# linearInjector_main.net
KiCad netlist of a schematic drawn in Altium Designer
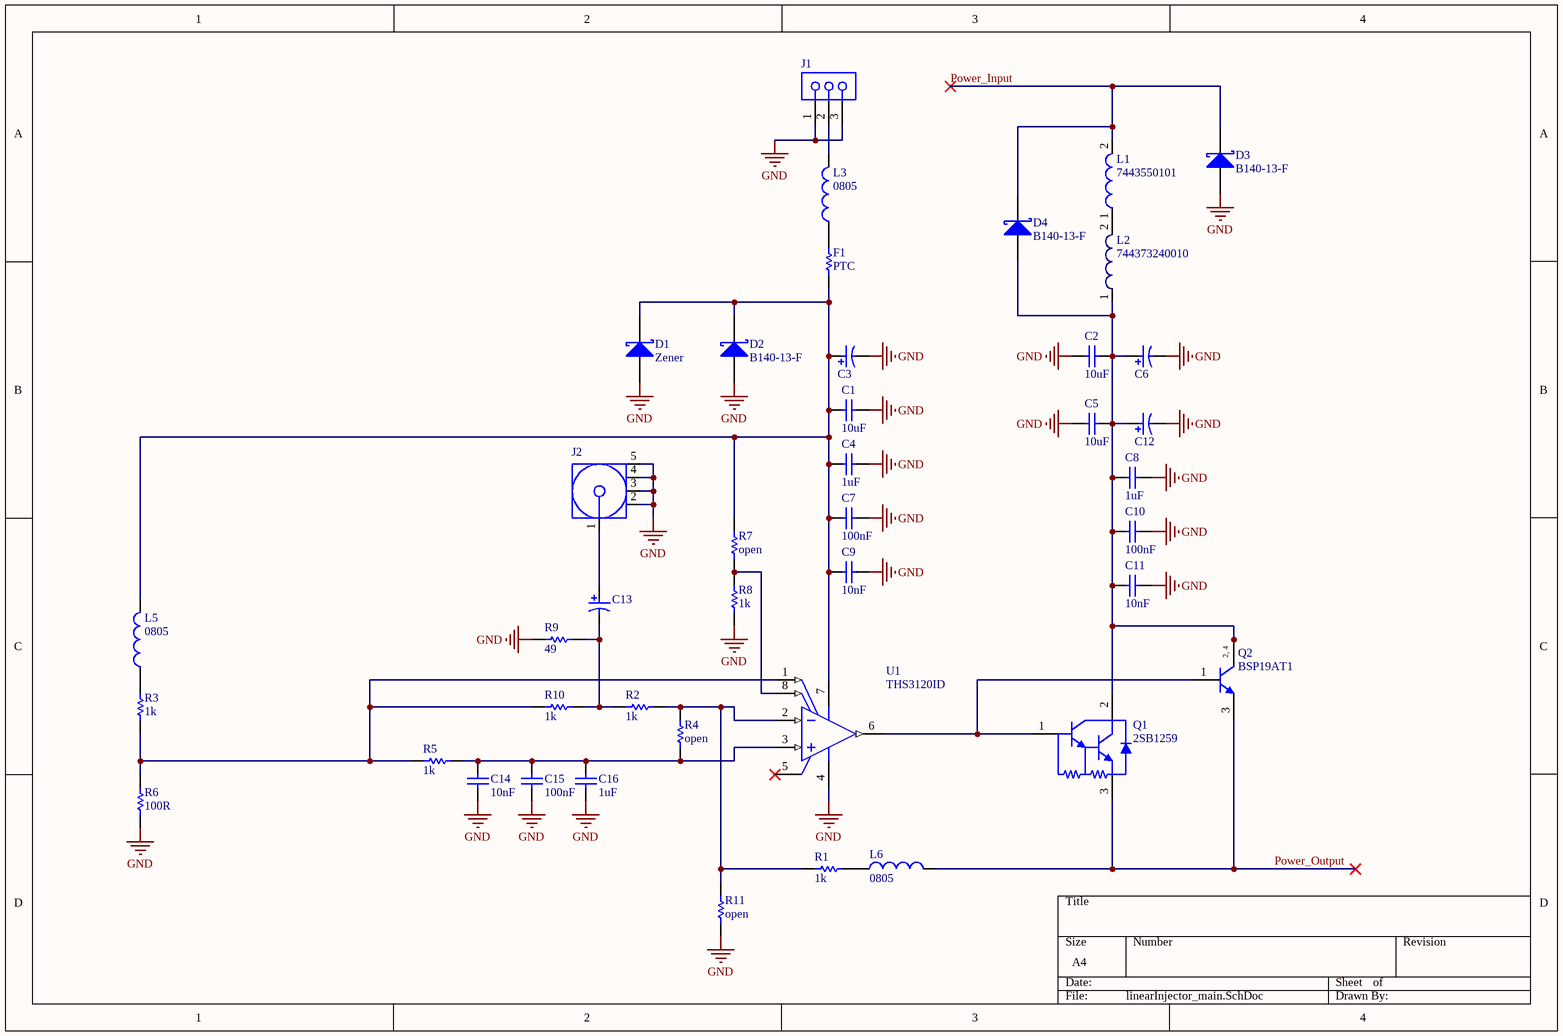
[diagram p0: linearInjector_main.SchDoc]

(export (version "E")
  (design (tool "Eeschema 10.0.6"))
  (components
    (comp (ref "C1")
      (value "10uF")
      (footprint "CAPC1206(3216)130_M")
      (fields (field (name "TOLERANCE") "-20% to +80%"))
      (libsource (lib "Altium Content Vault") (part "CAP"))
    )
    (comp (ref "C2")
      (value "10uF")
      (footprint "CAPC1206(3216)130_L")
      (fields (field (name "TOLERANCE") "-20% to +80%"))
      (libsource (lib "Altium Content Vault") (part "CAP"))
    )
    (comp (ref "C3")
      (value "alum")
      (footprint "PNSC-NF-A_V")
      (description "5mm lead pitch")
      (fields (field (name "VOLTAGE") "5.5Vdc") (field (name "TOLERANCE") "-20→+80%"))
      (libsource (lib "Altium Content Vault") (part "CAP-P-2"))
    )
    (comp (ref "C4")
      (value "1uF")
      (footprint "CAPC0805(2012)75_M")
      (fields (field (name "TOLERANCE") "-20% to +80%"))
      (libsource (lib "Altium Content Vault") (part "CAP"))
    )
    (comp (ref "C5")
      (value "10uF")
      (footprint "CAPC1206(3216)130_L")
      (fields (field (name "TOLERANCE") "-20% to +80%"))
      (libsource (lib "Altium Content Vault") (part "CAP"))
    )
    (comp (ref "C6")
      (value "alum")
      (footprint "PNSC-NF-A_V")
      (description "5mm lead pitch")
      (fields (field (name "VOLTAGE") "5.5Vdc") (field (name "TOLERANCE") "-20→+80%"))
      (libsource (lib "Altium Content Vault") (part "CAP-P-2"))
    )
    (comp (ref "C7")
      (value "100nF")
      (footprint "CAPC0805(2012)75_M")
      (fields (field (name "TOLERANCE") "-20% to +80%"))
      (libsource (lib "Altium Content Vault") (part "CAP"))
    )
    (comp (ref "C8")
      (value "1uF")
      (footprint "CAPC0805(2012)75_M")
      (fields (field (name "TOLERANCE") "-20% to +80%"))
      (libsource (lib "Altium Content Vault") (part "CAP"))
    )
    (comp (ref "C9")
      (value "10nF")
      (footprint "CAPC0805(2012)75_M")
      (fields (field (name "TOLERANCE") "-20% to +80%"))
      (libsource (lib "Altium Content Vault") (part "CAP"))
    )
    (comp (ref "C10")
      (value "100nF")
      (footprint "CAPC0805(2012)75_M")
      (fields (field (name "TOLERANCE") "-20% to +80%"))
      (libsource (lib "Altium Content Vault") (part "CAP"))
    )
    (comp (ref "C11")
      (value "10nF")
      (footprint "CAPC0805(2012)75_M")
      (fields (field (name "TOLERANCE") "-20% to +80%"))
      (libsource (lib "Altium Content Vault") (part "CAP"))
    )
    (comp (ref "C12")
      (value "alum")
      (footprint "PNSC-NF-A_V")
      (description "5mm lead pitch")
      (fields (field (name "VOLTAGE") "5.5Vdc") (field (name "TOLERANCE") "-20→+80%"))
      (libsource (lib "Altium Content Vault") (part "CAP-P-2"))
    )
    (comp (ref "C13")
      (value "alum")
      (footprint "PNSC-NF-A_V")
      (description "5mm lead pitch")
      (fields (field (name "VOLTAGE") "5.5Vdc") (field (name "TOLERANCE") "-20→+80%"))
      (libsource (lib "Altium Content Vault") (part "CAP-P-2"))
    )
    (comp (ref "C14")
      (value "10nF")
      (footprint "CAPC0805(2012)75_M")
      (fields (field (name "TOLERANCE") "-20% to +80%"))
      (libsource (lib "Altium Content Vault") (part "CAP"))
    )
    (comp (ref "C15")
      (value "100nF")
      (footprint "CAPC0805(2012)75_M")
      (fields (field (name "TOLERANCE") "-20% to +80%"))
      (libsource (lib "Altium Content Vault") (part "CAP"))
    )
    (comp (ref "C16")
      (value "1uF")
      (footprint "CAPC0805(2012)75_M")
      (fields (field (name "TOLERANCE") "-20% to +80%"))
      (libsource (lib "Altium Content Vault") (part "CAP"))
    )
    (comp (ref "D1")
      (value "Zener")
      (footprint "DIOD-B1X0-2_V")
      (description "option")
      (fields (field (name "MANUFACTURER") "DiodesIncorporated"))
      (libsource (lib "Altium Content Vault") (part "DSKY-KA-2"))
    )
    (comp (ref "D2")
      (value "B140-13-F")
      (footprint "DIOD-B1X0-2_V")
      (description "Surface Mount Schottky Barrier Rectifier, 1 A, -65 to 150 degC, 2-Pin SMA, RoHS, Tape and Reel")
      (fields (field (name "MANUFACTURER") "DiodesIncorporated"))
      (libsource (lib "Altium Content Vault") (part "DSKY-KA-2"))
    )
    (comp (ref "D3")
      (value "B140-13-F")
      (footprint "DIOD-B1X0-2_V")
      (description "Surface Mount Schottky Barrier Rectifier, 1 A, -65 to 150 degC, 2-Pin SMA, RoHS, Tape and Reel")
      (fields (field (name "MANUFACTURER") "DiodesIncorporated"))
      (libsource (lib "Altium Content Vault") (part "DSKY-KA-2"))
    )
    (comp (ref "D4")
      (value "B140-13-F")
      (footprint "DIOD-B1X0-2_V")
      (description "Surface Mount Schottky Barrier Rectifier, 1 A, -65 to 150 degC, 2-Pin SMA, RoHS, Tape and Reel")
      (fields (field (name "MANUFACTURER") "DiodesIncorporated"))
      (libsource (lib "Altium Content Vault") (part "DSKY-KA-2"))
    )
    (comp (ref "F1")
      (value "PTC")
      (footprint "RESC1206(3216)_M")
      (description "Fuse")
      (fields (field (name "TOLERANCE") "1 %") (field (name "POWER") "0.25 W"))
      (libsource (lib "Altium Content Vault") (part "RES"))
    )
    (comp (ref "J1")
      (value "BCS-103-L-S-TE")
      (footprint "SMTC-BCS-103-X-S-TE")
      (description "Tiger Claw(TM) Pass-Through Socket, Vertical, -55 to 125 degC, 2.54 mm Pitch, 3-Pin, Female, RoHS")
      (fields (field (name "MANUFACTURER") "Samtec"))
      (libsource (lib "Altium Content Vault") (part "SMTC-BCS-103-X-S-TE"))
    )
    (comp (ref "J2")
      (value "LTI-SASF54GT")
      (footprint "LHT-LTI-SASF54GT_V")
      (description "SMA Connector, Pitch 2.54 mm, 1 Position, Height 9.5 mm, Tail Length 4 mm, RoHS")
      (fields (field (name "MANUFACTURER") "Lighthorse Technologies Inc."))
      (libsource (lib "Altium Content Vault") (part "CN-S-F-RF5"))
    )
    (comp (ref "L1")
      (value "7443550101")
      (footprint "WE-HCI-1350")
      (description "SMD Flat Wire High Current Inductor WE-HCI, L=10.0 µH")
      (libsource (lib "Altium Content Vault") (part "PAS-IND-INDUCTOR-2"))
    )
    (comp (ref "L2")
      (value "744373240010")
      (footprint "WE-LHMI 4020")
      (description "SMD Power Inductor WE-LHMI, L=0.10 µH")
      (fields (field (name "MANUFACTURER") "Wuerth Elektronik"))
      (libsource (lib "Altium Content Vault") (part "WE-IND-INDUCTOR-2"))
    )
    (comp (ref "L3")
      (value "0805")
      (footprint "INDC2013X105X50ML20T30")
      (fields (field (name "TOLERANCE") "30%"))
      (libsource (lib "Altium Content Vault") (part "IND-2"))
    )
    (comp (ref "L5")
      (value "0805")
      (footprint "INDC2013X105X50ML20T30")
      (fields (field (name "TOLERANCE") "30%"))
      (libsource (lib "Altium Content Vault") (part "IND-2"))
    )
    (comp (ref "L6")
      (value "0805")
      (footprint "INDC2013X105X50ML20T30")
      (fields (field (name "TOLERANCE") "30%"))
      (libsource (lib "Altium Content Vault") (part "IND-2"))
    )
    (comp (ref "Q1")
      (value "2SB1259")
      (footprint "ONSC-TO-220-3-221A-09")
      (fields (field (name "PARTNUMBER") "MJE5740G") (field (name "MANUFACTURER") "On Semiconductor"))
      (libsource (lib "Altium Content Vault") (part "ONSC-DT-NPN-B1C2E3-3_A"))
    )
    (comp (ref "Q2")
      (value "BSP19AT1")
      (footprint "ONSC-SOT-223-4-318E-04_V")
      (description "NPN Silicon Expitaxial Transistor, 4-Pin SOT-223, Tape and Reel")
      (fields (field (name "MANUFACTURER") "On Semiconductor"))
      (libsource (lib "Altium Content Vault") (part "ONSC-NPN-B1C2E3C4-4"))
    )
    (comp (ref "R1")
      (value "1k")
      (footprint "RESC0805(2012)_M")
      (description "1k 1%")
      (fields (field (name "TOLERANCE") "1 %") (field (name "POWER") "0.125 W"))
      (libsource (lib "Altium Content Vault") (part "RES"))
    )
    (comp (ref "R2")
      (value "1k")
      (footprint "RESC0805(2012)_M")
      (description "1k 1%")
      (fields (field (name "TOLERANCE") "1 %") (field (name "POWER") "0.125 W"))
      (libsource (lib "Altium Content Vault") (part "RES"))
    )
    (comp (ref "R3")
      (value "1k")
      (footprint "RESC0805(2012)_M")
      (description "1k 1%")
      (fields (field (name "TOLERANCE") "1 %") (field (name "POWER") "0.125 W"))
      (libsource (lib "Altium Content Vault") (part "RES"))
    )
    (comp (ref "R4")
      (value "open")
      (footprint "RESC0805(2012)_M")
      (fields (field (name "TOLERANCE") "1 %") (field (name "POWER") "0.125 W"))
      (libsource (lib "Altium Content Vault") (part "RES"))
    )
    (comp (ref "R5")
      (value "1k")
      (footprint "RESC0805(2012)_M")
      (description "1k 1%")
      (fields (field (name "TOLERANCE") "1 %") (field (name "POWER") "0.125 W"))
      (libsource (lib "Altium Content Vault") (part "RES"))
    )
    (comp (ref "R6")
      (value "100R")
      (footprint "RESC0805(2012)_M")
      (description "1k 1%")
      (fields (field (name "TOLERANCE") "1 %") (field (name "POWER") "0.125 W"))
      (libsource (lib "Altium Content Vault") (part "RES"))
    )
    (comp (ref "R7")
      (value "open")
      (footprint "RESC0805(2012)_M")
      (description "1k 1%")
      (fields (field (name "TOLERANCE") "1 %") (field (name "POWER") "0.125 W"))
      (libsource (lib "Altium Content Vault") (part "RES"))
    )
    (comp (ref "R8")
      (value "1k")
      (footprint "RESC0805(2012)_M")
      (description "1k 1%")
      (fields (field (name "TOLERANCE") "1 %") (field (name "POWER") "0.125 W"))
      (libsource (lib "Altium Content Vault") (part "RES"))
    )
    (comp (ref "R9")
      (value "49")
      (footprint "RESC0805(2012)_M")
      (description "1k 1%")
      (fields (field (name "TOLERANCE") "1 %") (field (name "POWER") "0.125 W"))
      (libsource (lib "Altium Content Vault") (part "RES"))
    )
    (comp (ref "R10")
      (value "1k")
      (footprint "RESC0805(2012)_M")
      (description "1k 1%")
      (fields (field (name "TOLERANCE") "1 %") (field (name "POWER") "0.125 W"))
      (libsource (lib "Altium Content Vault") (part "RES"))
    )
    (comp (ref "R11")
      (value "open")
      (footprint "RESC0805(2012)_M")
      (description "1k 1%")
      (fields (field (name "TOLERANCE") "1 %") (field (name "POWER") "0.125 W"))
      (libsource (lib "Altium Content Vault") (part "RES"))
    )
    (comp (ref "U1")
      (value "THS3120ID")
      (footprint "D0008A_L")
      (fields (field (name "MANUFACTURER") "Texas Instruments"))
      (libsource (lib "Altium Content Vault") (part "TI-THS3110_3120D8"))
    )
  )
  (nets
    (net (code "1") (name "/Power_Input") (class "Default")
      (node (ref "D3") (pin "1") (pinfunction "K_1") (pintype "passive"))
      (node (ref "D4") (pin "1") (pinfunction "K_1") (pintype "passive"))
      (node (ref "L1") (pin "2") (pinfunction "2_2") (pintype "passive"))
    )
    (net (code "2") (name "/Power_Output") (class "Default")
      (node (ref "L6") (pin "2") (pinfunction "2_2") (pintype "passive"))
      (node (ref "Q1") (pin "3") (pinfunction "E_3") (pintype "passive"))
      (node (ref "Q2") (pin "3") (pinfunction "E_3") (pintype "passive"))
    )
    (net (code "3") (name "GND") (class "Default")
      (node (ref "C1") (pin "2") (pinfunction "2_2") (pintype "passive"))
      (node (ref "C10") (pin "1") (pinfunction "1_1") (pintype "passive"))
      (node (ref "C11") (pin "1") (pinfunction "1_1") (pintype "passive"))
      (node (ref "C12") (pin "2") (pinfunction "2_2") (pintype "passive"))
      (node (ref "C14") (pin "1") (pinfunction "1_1") (pintype "passive"))
      (node (ref "C15") (pin "1") (pinfunction "1_1") (pintype "passive"))
      (node (ref "C16") (pin "1") (pinfunction "1_1") (pintype "passive"))
      (node (ref "C2") (pin "2") (pinfunction "2_2") (pintype "passive"))
      (node (ref "C3") (pin "2") (pinfunction "2_2") (pintype "passive"))
      (node (ref "C4") (pin "1") (pinfunction "1_1") (pintype "passive"))
      (node (ref "C5") (pin "2") (pinfunction "2_2") (pintype "passive"))
      (node (ref "C6") (pin "2") (pinfunction "2_2") (pintype "passive"))
      (node (ref "C7") (pin "1") (pinfunction "1_1") (pintype "passive"))
      (node (ref "C8") (pin "1") (pinfunction "1_1") (pintype "passive"))
      (node (ref "C9") (pin "1") (pinfunction "1_1") (pintype "passive"))
      (node (ref "D1") (pin "2") (pinfunction "A_2") (pintype "passive"))
      (node (ref "D2") (pin "2") (pinfunction "A_2") (pintype "passive"))
      (node (ref "D3") (pin "2") (pinfunction "A_2") (pintype "passive"))
      (node (ref "J1") (pin "1") (pinfunction "1_1") (pintype "passive"))
      (node (ref "J1") (pin "3") (pinfunction "3_3") (pintype "passive"))
      (node (ref "J2") (pin "2") (pinfunction "2_2") (pintype "passive"))
      (node (ref "J2") (pin "3") (pinfunction "3_3") (pintype "passive"))
      (node (ref "J2") (pin "4") (pinfunction "4_4") (pintype "passive"))
      (node (ref "J2") (pin "5") (pinfunction "5_5") (pintype "passive"))
      (node (ref "R11") (pin "1") (pinfunction "1_1") (pintype "passive"))
      (node (ref "R6") (pin "1") (pinfunction "1_1") (pintype "passive"))
      (node (ref "R8") (pin "1") (pinfunction "1_1") (pintype "passive"))
      (node (ref "R9") (pin "1") (pinfunction "1_1") (pintype "passive"))
      (node (ref "U1") (pin "4") (pinfunction "VS-_4") (pintype "power_in"))
    )
    (net (code "4") (name "Net-(C13-Pad1)") (class "Default")
      (node (ref "C13") (pin "1") (pinfunction "1_1") (pintype "passive"))
      (node (ref "J2") (pin "1") (pinfunction "1_1") (pintype "passive"))
    )
    (net (code "5") (name "Net-(C13-Pad2)") (class "Default")
      (node (ref "C13") (pin "2") (pinfunction "2_2") (pintype "passive"))
      (node (ref "R10") (pin "2") (pinfunction "2_2") (pintype "passive"))
      (node (ref "R2") (pin "1") (pinfunction "1_1") (pintype "passive"))
      (node (ref "R9") (pin "2") (pinfunction "2_2") (pintype "passive"))
    )
    (net (code "6") (name "Net-(D1-K)") (class "Default")
      (node (ref "C1") (pin "1") (pinfunction "1_1") (pintype "passive"))
      (node (ref "C3") (pin "1") (pinfunction "1_1") (pintype "passive"))
      (node (ref "C4") (pin "2") (pinfunction "2_2") (pintype "passive"))
      (node (ref "C7") (pin "2") (pinfunction "2_2") (pintype "passive"))
      (node (ref "C9") (pin "2") (pinfunction "2_2") (pintype "passive"))
      (node (ref "D1") (pin "1") (pinfunction "K_1") (pintype "passive"))
      (node (ref "D2") (pin "1") (pinfunction "K_1") (pintype "passive"))
      (node (ref "F1") (pin "1") (pinfunction "1_1") (pintype "passive"))
      (node (ref "L5") (pin "2") (pinfunction "2_2") (pintype "passive"))
      (node (ref "R7") (pin "2") (pinfunction "2_2") (pintype "passive"))
      (node (ref "U1") (pin "7") (pinfunction "VS+_7") (pintype "power_in"))
    )
    (net (code "7") (name "Net-(D4-A)") (class "Default")
      (node (ref "C10") (pin "2") (pinfunction "2_2") (pintype "passive"))
      (node (ref "C11") (pin "2") (pinfunction "2_2") (pintype "passive"))
      (node (ref "C12") (pin "1") (pinfunction "1_1") (pintype "passive"))
      (node (ref "C2") (pin "1") (pinfunction "1_1") (pintype "passive"))
      (node (ref "C5") (pin "1") (pinfunction "1_1") (pintype "passive"))
      (node (ref "C6") (pin "1") (pinfunction "1_1") (pintype "passive"))
      (node (ref "C8") (pin "2") (pinfunction "2_2") (pintype "passive"))
      (node (ref "D4") (pin "2") (pinfunction "A_2") (pintype "passive"))
      (node (ref "L2") (pin "1") (pinfunction "1_1") (pintype "passive"))
      (node (ref "Q1") (pin "2") (pinfunction "C_2") (pintype "passive"))
      (node (ref "Q2") (pin "2") (pinfunction "C_2") (pintype "passive"))
      (node (ref "Q2") (pin "4") (pinfunction "C_4") (pintype "passive"))
    )
    (net (code "8") (name "Net-(F1-Pad2)") (class "Default")
      (node (ref "F1") (pin "2") (pinfunction "2_2") (pintype "passive"))
      (node (ref "L3") (pin "1") (pinfunction "1_1") (pintype "passive"))
    )
    (net (code "9") (name "Net-(J1-Pad2)") (class "Default")
      (node (ref "J1") (pin "2") (pinfunction "2_2") (pintype "passive"))
      (node (ref "L3") (pin "2") (pinfunction "2_2") (pintype "passive"))
    )
    (net (code "10") (name "Net-(L1-Pad1)") (class "Default")
      (node (ref "L1") (pin "1") (pinfunction "1_1") (pintype "passive"))
      (node (ref "L2") (pin "2") (pinfunction "2_2") (pintype "passive"))
    )
    (net (code "11") (name "Net-(L5-Pad1)") (class "Default")
      (node (ref "L5") (pin "1") (pinfunction "1_1") (pintype "passive"))
      (node (ref "R3") (pin "2") (pinfunction "2_2") (pintype "passive"))
    )
    (net (code "12") (name "Net-(L6-Pad1)") (class "Default")
      (node (ref "L6") (pin "1") (pinfunction "1_1") (pintype "passive"))
      (node (ref "R1") (pin "2") (pinfunction "2_2") (pintype "passive"))
    )
    (net (code "13") (name "Net-(Q1-B)") (class "Default")
      (node (ref "Q1") (pin "1") (pinfunction "B_1") (pintype "passive"))
      (node (ref "Q2") (pin "1") (pinfunction "B_1") (pintype "passive"))
      (node (ref "U1") (pin "6") (pinfunction "VOUT_6") (pintype "output"))
    )
    (net (code "14") (name "Net-(U1-PD)") (class "Default")
      (node (ref "R7") (pin "1") (pinfunction "1_1") (pintype "passive"))
      (node (ref "R8") (pin "2") (pinfunction "2_2") (pintype "passive"))
      (node (ref "U1") (pin "8") (pinfunction "PD_8") (pintype "input"))
    )
    (net (code "15") (name "Net-(U1-REF)") (class "Default")
      (node (ref "R10") (pin "1") (pinfunction "1_1") (pintype "passive"))
      (node (ref "R3") (pin "1") (pinfunction "1_1") (pintype "passive"))
      (node (ref "R5") (pin "1") (pinfunction "1_1") (pintype "passive"))
      (node (ref "R6") (pin "2") (pinfunction "2_2") (pintype "passive"))
      (node (ref "U1") (pin "1") (pinfunction "REF_1") (pintype "input"))
    )
    (net (code "16") (name "Net-(U1-VIN+)") (class "Default")
      (node (ref "C14") (pin "2") (pinfunction "2_2") (pintype "passive"))
      (node (ref "C15") (pin "2") (pinfunction "2_2") (pintype "passive"))
      (node (ref "C16") (pin "2") (pinfunction "2_2") (pintype "passive"))
      (node (ref "R4") (pin "1") (pinfunction "1_1") (pintype "passive"))
      (node (ref "R5") (pin "2") (pinfunction "2_2") (pintype "passive"))
      (node (ref "U1") (pin "3") (pinfunction "VIN+_3") (pintype "input"))
    )
    (net (code "17") (name "Net-(U1-VIN-)") (class "Default")
      (node (ref "R1") (pin "1") (pinfunction "1_1") (pintype "passive"))
      (node (ref "R11") (pin "2") (pinfunction "2_2") (pintype "passive"))
      (node (ref "R2") (pin "2") (pinfunction "2_2") (pintype "passive"))
      (node (ref "R4") (pin "2") (pinfunction "2_2") (pintype "passive"))
      (node (ref "U1") (pin "2") (pinfunction "VIN-_2") (pintype "input"))
    )
    (net (code "18") (name "unconnected-(U1-NC-Pad5)") (class "Default")
      (node (ref "U1") (pin "5") (pinfunction "NC_5") (pintype "passive+no_connect"))
    )
  )
)
